# Accelerometer.net
KiCad netlist of a schematic drawn in Altium Designer
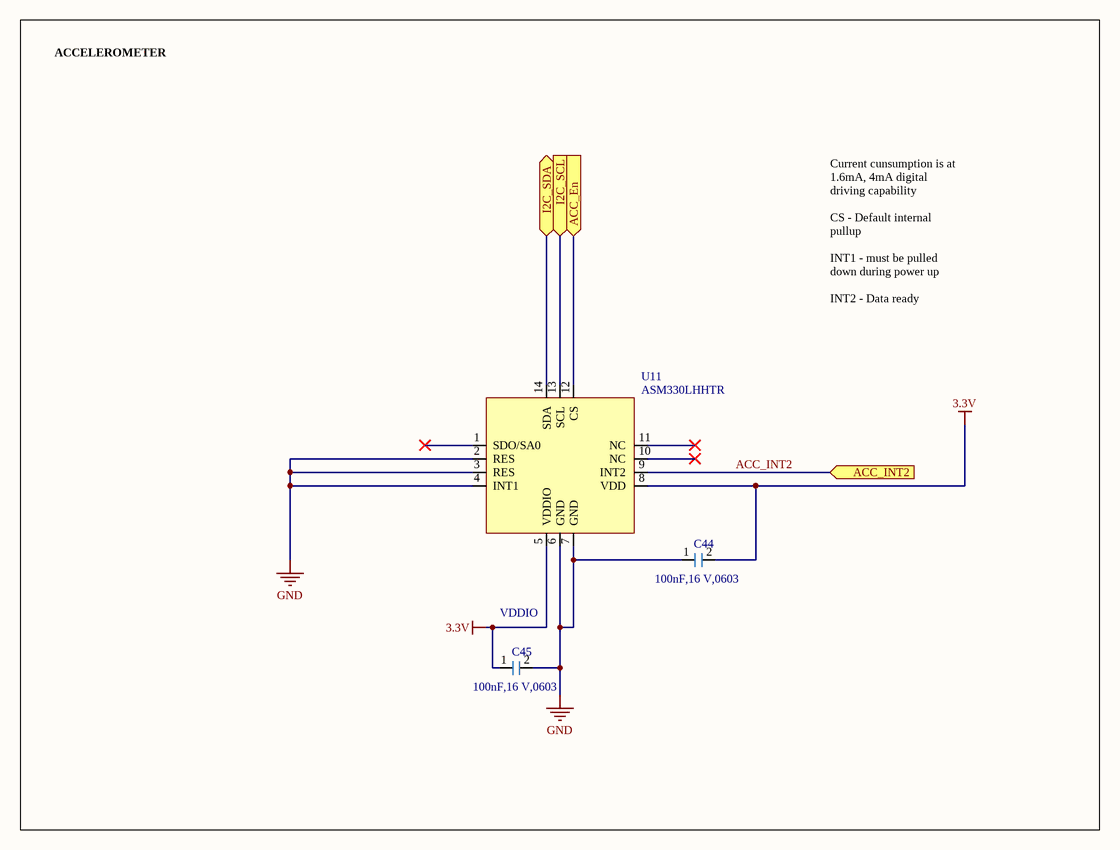
[diagram p0: Accelerometer.SchDoc]

(export (version "E")
  (design (tool "Eeschema 10.0.6"))
  (components
    (comp (ref "C44")
      (value "CC0603KRX7R7BB104")
      (footprint "BMS_V2.1_Adv:CAPC1608X05N 0603")
      (description "Multilayer Ceramic Capacitor, 100 nF, 16V, ±10%,  X7R 0603 [1608 Metric]")
      (fields
        (field (name "MANUFACTURER") "Yageo")
        (field (name "TOLERANCE") "10%")
        (field (name "VALUE DISPLAY") "100nF,16 V,0603")
      )
      (libsource (lib "BMS_V2.1_Adv") (part "Cap_CC0603KRX7R7BB104"))
    )
    (comp (ref "C45")
      (value "CC0603KRX7R7BB104")
      (footprint "BMS_V2.1_Adv:CAPC1608X05N 0603")
      (description "Multilayer Ceramic Capacitor, 100 nF, 16V, ±10%,  X7R 0603 [1608 Metric]")
      (fields
        (field (name "MANUFACTURER") "Yageo")
        (field (name "TOLERANCE") "10%")
        (field (name "VALUE DISPLAY") "100nF,16 V,0603")
      )
      (libsource (lib "BMS_V2.1_Adv") (part "Cap_CC0603KRX7R7BB104"))
    )
    (comp (ref "U11")
      (value "ASM330LHHTR")
      (footprint "BMS_V2.1_Adv:QFN50P300X250X86-14N_ASM330LHHTR")
      (description "Accelerometer, Gyroscope, Temperature, 6 Axis Sensor I2C, SPI Output")
      (fields (field (name "MANUFACTURER") "ST") (field (name "VOLTAGE") "3.3V"))
      (libsource (lib "BMS_V2.1_Adv") (part "IC_ASM330LHHTR"))
    )
  )
  (nets
    (net (code "1") (name "/ACC_En") (class "Default")
      (node (ref "U11") (pin "12") (pinfunction "CS_12") (pintype "passive"))
    )
    (net (code "2") (name "/ACC_INT2") (class "Default")
      (node (ref "U11") (pin "9") (pinfunction "INT2_9") (pintype "passive"))
    )
    (net (code "3") (name "/I2C_SCL") (class "Default")
      (node (ref "U11") (pin "13") (pinfunction "SCL_13") (pintype "passive"))
    )
    (net (code "4") (name "/I2C_SDA") (class "Default")
      (node (ref "U11") (pin "14") (pinfunction "SDA_14") (pintype "passive"))
    )
    (net (code "5") (name "3.3V") (class "Default")
      (node (ref "C44") (pin "2") (pinfunction "2_2") (pintype "passive"))
      (node (ref "C45") (pin "1") (pinfunction "1_1") (pintype "passive"))
      (node (ref "U11") (pin "5") (pinfunction "VDDIO_5") (pintype "passive"))
      (node (ref "U11") (pin "8") (pinfunction "VDD_8") (pintype "passive"))
    )
    (net (code "6") (name "GND") (class "Default")
      (node (ref "C44") (pin "1") (pinfunction "1_1") (pintype "passive"))
      (node (ref "C45") (pin "2") (pinfunction "2_2") (pintype "passive"))
      (node (ref "U11") (pin "2") (pinfunction "RES_2") (pintype "passive"))
      (node (ref "U11") (pin "3") (pinfunction "RES_3") (pintype "passive"))
      (node (ref "U11") (pin "4") (pinfunction "INT1_4") (pintype "passive"))
      (node (ref "U11") (pin "6") (pinfunction "GND_6") (pintype "passive"))
      (node (ref "U11") (pin "7") (pinfunction "GND_7") (pintype "passive"))
    )
    (net (code "7") (name "unconnected-(U11-NC-Pad10)") (class "Default")
      (node (ref "U11") (pin "10") (pinfunction "NC_10") (pintype "passive+no_connect"))
    )
    (net (code "8") (name "unconnected-(U11-NC-Pad11)") (class "Default")
      (node (ref "U11") (pin "11") (pinfunction "NC_11") (pintype "passive+no_connect"))
    )
    (net (code "9") (name "unconnected-(U11-SDO{slash}SA0-Pad1)") (class "Default")
      (node (ref "U11") (pin "1") (pinfunction "SDO/SA0_1") (pintype "passive+no_connect"))
    )
  )
)
